# SCH_SGU-Ring.net
KiCad netlist of a schematic drawn in EasyEDA
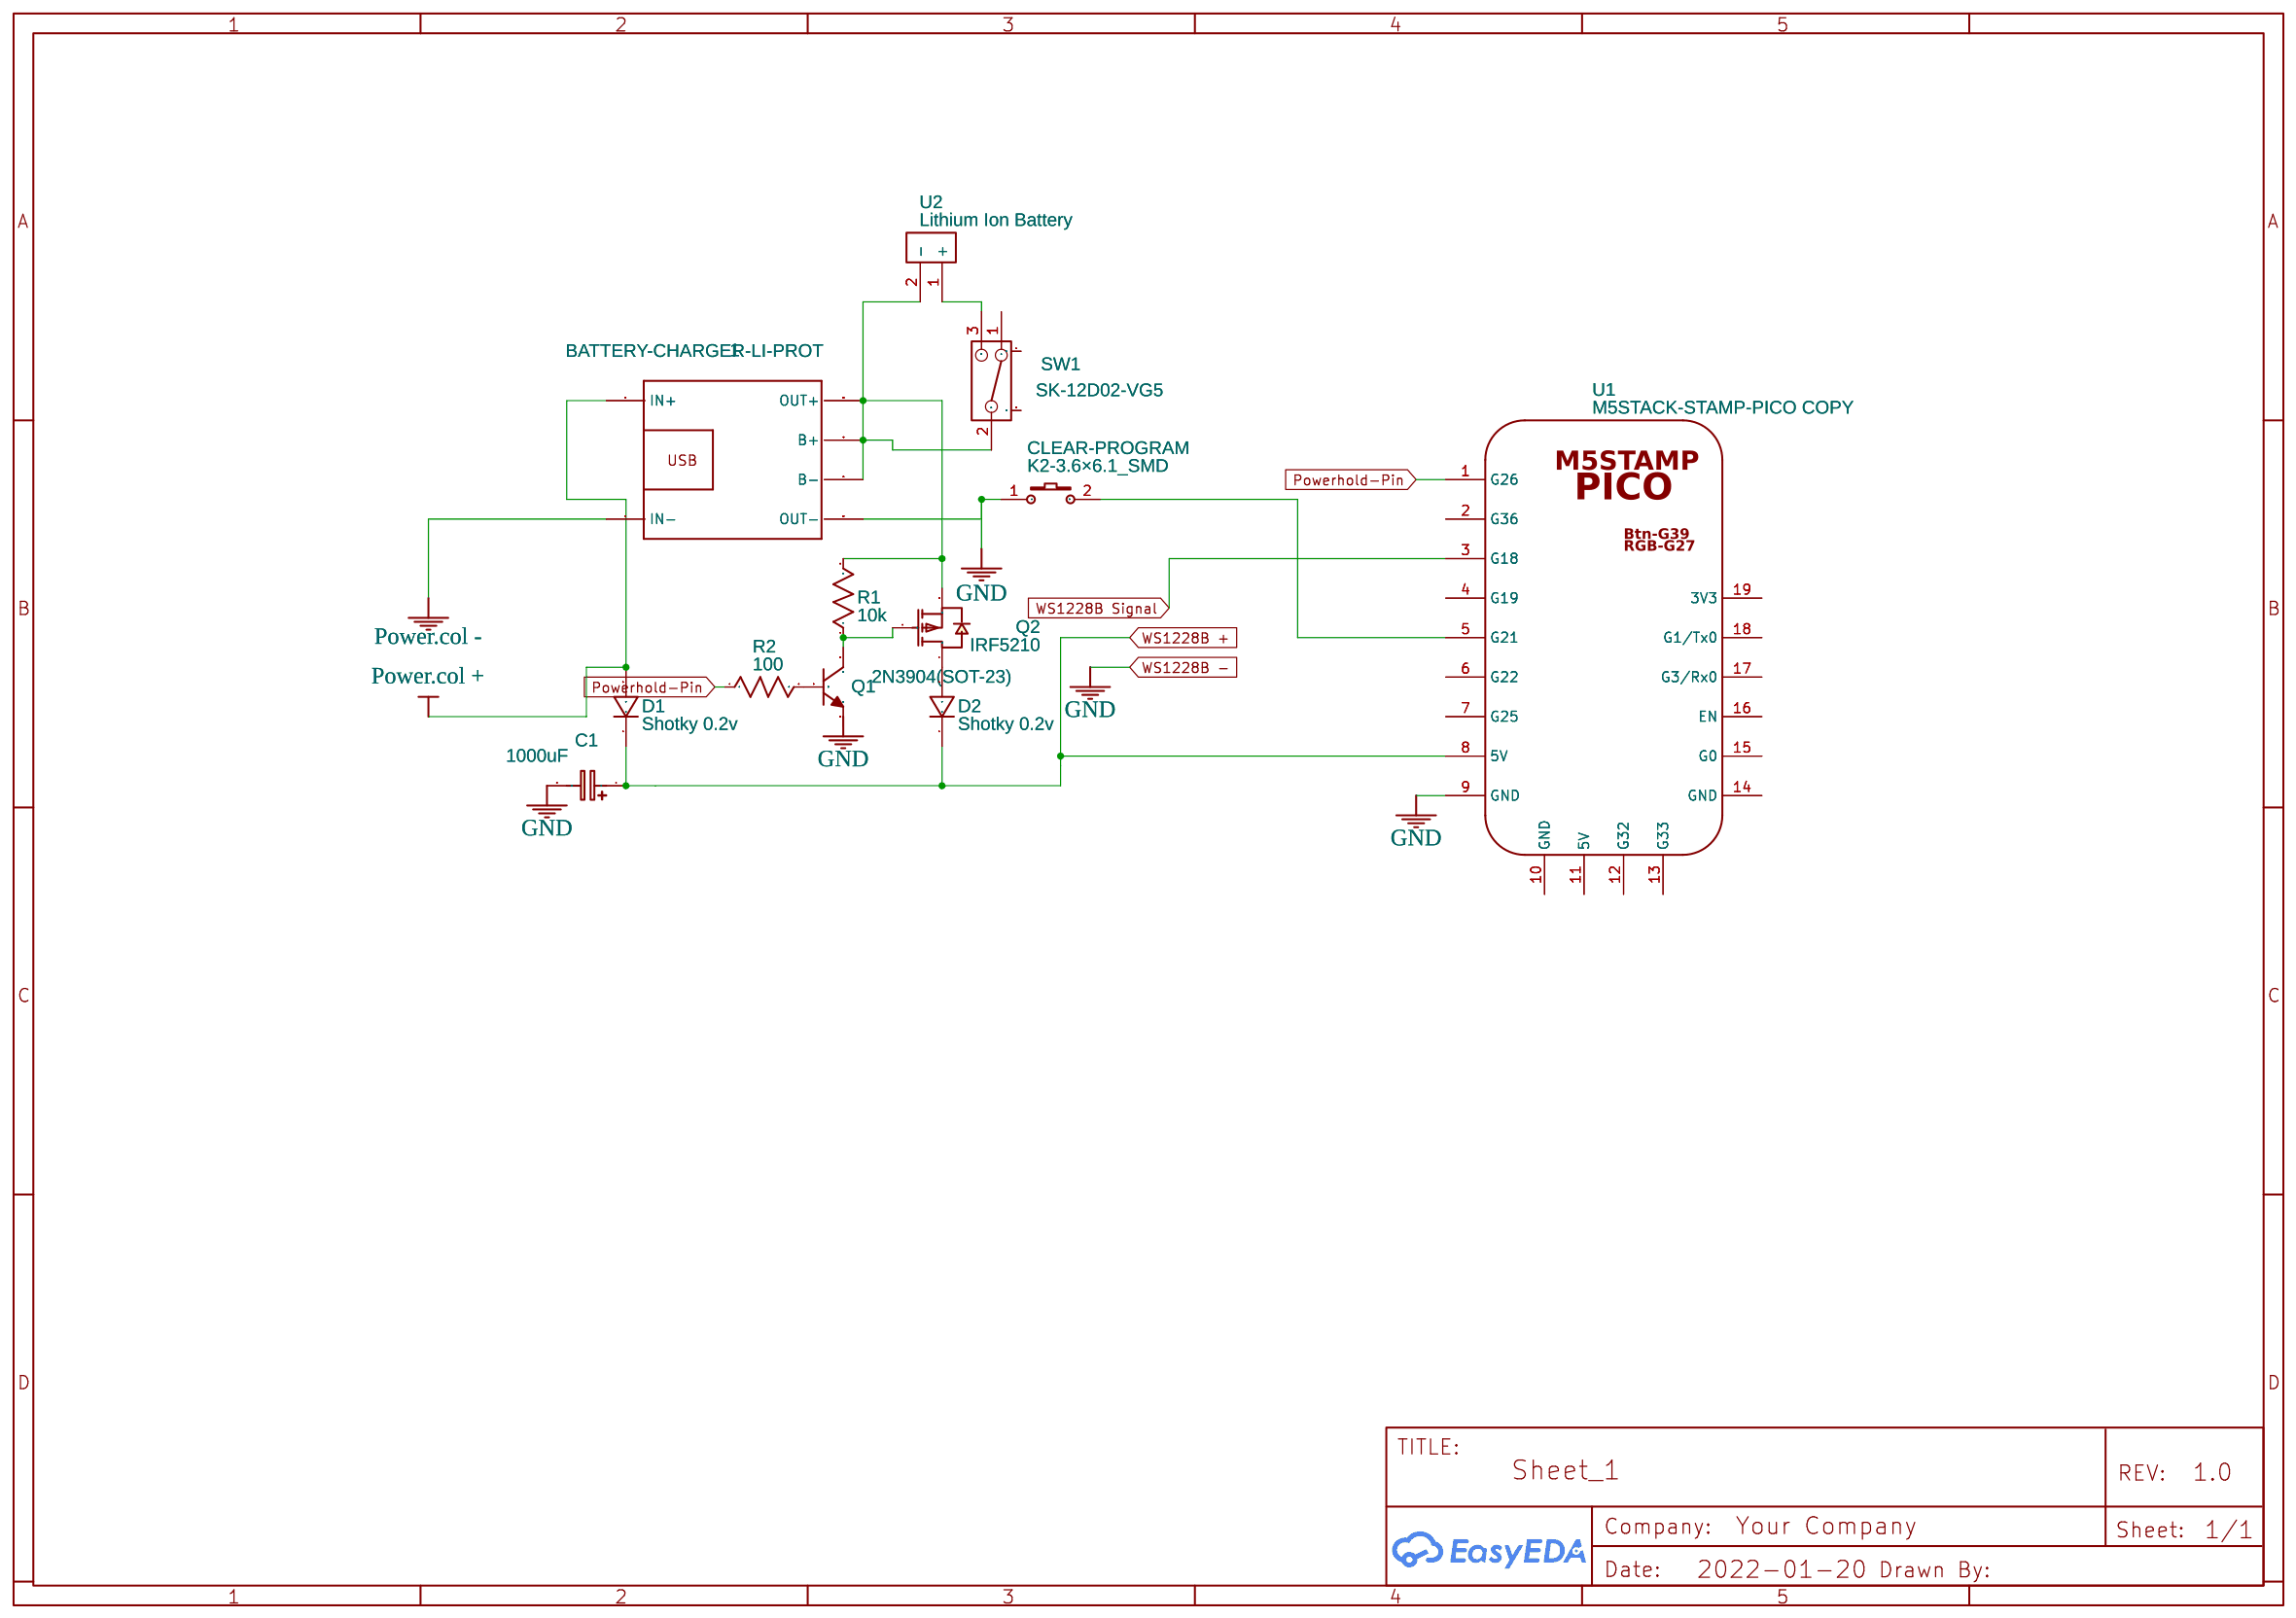
[diagram p0: schematic sheet]

(export (version "E")
  (design (tool "Eeschema 10.0.6"))
  (components
    (comp (ref "1") (value "BATTERY-CHARGER-LI-PROT") (libsource (lib "") (part "BATTERY-CHARGER-LI-PROT")))
    (comp (ref "C1") (value "1000uF") (libsource (lib "") (part "C_Tan_SMD_A_EU")))
    (comp (ref "CLEAR-PROGRAM")
      (value "K2-3.6×6.1_SMD")
      (fields
        (field (name "BOM_Manufacturer Part") "K2-1107ST-A4SW-06")
        (field (name "BOM_Supplier Part") "C118141")
      )
      (libsource (lib "") (part "K2-3.6×6.1_SMD"))
    )
    (comp (ref "D1")
      (value "Shotky 0.2v")
      (fields (field (name "BOM_Manufacturer Part") "1N4007W") (field (name "BOM_Supplier Part") "C328592"))
      (libsource (lib "") (part "1N4007W"))
    )
    (comp (ref "D2")
      (value "Shotky 0.2v")
      (fields (field (name "BOM_Manufacturer Part") "1N4007W") (field (name "BOM_Supplier Part") "C328592"))
      (libsource (lib "") (part "1N4007W"))
    )
    (comp (ref "Q1")
      (value "2N3904(SOT-23)")
      (fields
        (field (name "BOM_Manufacturer Part") "2n3904S-RTK/PS")
        (field (name "BOM_Supplier Part") "C18536")
      )
      (libsource (lib "") (part "2N3904(SOT-23)"))
    )
    (comp (ref "Q2")
      (value "IRF5210")
      (fields
        (field (name "BOM_Manufacturer Part") "IRF5210STRLPBF")
        (field (name "BOM_Supplier Part") "C2622")
      )
      (libsource (lib "") (part "IRF5210"))
    )
    (comp (ref "R1") (value "10k") (libsource (lib "") (part "R_0603_US")))
    (comp (ref "R2") (value "100") (libsource (lib "") (part "R_0603_US_1")))
    (comp (ref "SW1")
      (value "SK-12D02-VG5")
      (fields (field (name "BOM_Supplier Part") "C136722"))
      (libsource (lib "") (part "SK-12D02-VG5"))
    )
    (comp (ref "U1") (value "M5STACK-STAMP-PICO COPY") (libsource (lib "") (part "M5STACK-STAMP-PICO COPY")))
    (comp (ref "U2") (value "Lithium Ion Battery") (libsource (lib "") (part "Lithium Ion Battery")))
  )
  (nets
    (net (code "1") (name "Net-(Q1-B)") (class "Default")
      (node (ref "Q1") (pin "2") (pinfunction "B_2") (pintype "input"))
      (node (ref "R2") (pin "2") (pinfunction "2_2") (pintype "unspecified"))
    )
    (net (code "2") (name "Net-(Q1-C)") (class "Default")
      (node (ref "Q1") (pin "3") (pinfunction "C_3") (pintype "input"))
      (node (ref "Q2") (pin "1") (pinfunction "G_1") (pintype "unspecified"))
      (node (ref "R1") (pin "1") (pinfunction "1_1") (pintype "unspecified"))
    )
    (net (code "3") (name "Net-(Q2-D)") (class "Default")
      (node (ref "D2") (pin "2") (pinfunction "2_2") (pintype "unspecified"))
      (node (ref "Q2") (pin "4") (pinfunction "D_4") (pintype "unspecified"))
    )
    (net (code "4") (name "Net-(Q2-S)") (class "Default")
      (node (ref "1") (pin "B+") (pinfunction "B+_B+") (pintype "bidirectional"))
      (node (ref "1") (pin "B-") (pinfunction "B-_B-") (pintype "bidirectional"))
      (node (ref "1") (pin "OUT+") (pinfunction "OUT+_OUT+") (pintype "bidirectional"))
      (node (ref "Q2") (pin "3") (pinfunction "S_3") (pintype "unspecified"))
      (node (ref "R1") (pin "2") (pinfunction "2_2") (pintype "unspecified"))
      (node (ref "SW1") (pin "2") (pinfunction "2_2") (pintype "unspecified"))
      (node (ref "U2") (pin "2") (pinfunction "-_2") (pintype "unspecified"))
    )
    (net (code "5") (name "Net-(U1-G21)") (class "Default")
      (node (ref "CLEAR-PROGRAM") (pin "2") (pinfunction "2_2") (pintype "unspecified"))
      (node (ref "U1") (pin "5") (pinfunction "G21_5") (pintype "unspecified"))
    )
    (net (code "6") (name "Net-(U2-+)") (class "Default")
      (node (ref "SW1") (pin "3") (pinfunction "3_3") (pintype "unspecified"))
      (node (ref "U2") (pin "1") (pinfunction "+_1") (pintype "unspecified"))
    )
    (net (code "7") (name "Power.col +") (class "Default")
      (node (ref "1") (pin "IN+") (pinfunction "IN+_IN+") (pintype "bidirectional"))
      (node (ref "D1") (pin "2") (pinfunction "2_2") (pintype "unspecified"))
    )
    (net (code "8") (name "Power.col -") (class "Default")
      (node (ref "1") (pin "IN-") (pinfunction "IN-_IN-") (pintype "bidirectional"))
    )
    (net (code "9") (name "Powerhold-Pin") (class "Default")
      (node (ref "R2") (pin "1") (pinfunction "1_1") (pintype "unspecified"))
      (node (ref "U1") (pin "1") (pinfunction "G26_1") (pintype "unspecified"))
    )
    (net (code "10") (name "WS1228B +") (class "Default")
      (node (ref "C1") (pin "1") (pinfunction "1_1") (pintype "unspecified"))
      (node (ref "D1") (pin "1") (pinfunction "1_1") (pintype "unspecified"))
      (node (ref "D2") (pin "1") (pinfunction "1_1") (pintype "unspecified"))
      (node (ref "U1") (pin "8") (pinfunction "5V_8") (pintype "unspecified"))
    )
    (net (code "11") (name "WS1228B -") (class "Default")
      (node (ref "1") (pin "OUT-") (pinfunction "OUT-_OUT-") (pintype "bidirectional"))
      (node (ref "C1") (pin "2") (pinfunction "2_2") (pintype "unspecified"))
      (node (ref "CLEAR-PROGRAM") (pin "1") (pinfunction "1_1") (pintype "unspecified"))
      (node (ref "Q1") (pin "1") (pinfunction "E_1") (pintype "input"))
      (node (ref "U1") (pin "9") (pinfunction "GND_9") (pintype "unspecified"))
    )
    (net (code "12") (name "WS1228B Signal") (class "Default")
      (node (ref "U1") (pin "3") (pinfunction "G18_3") (pintype "unspecified"))
    )
    (net (code "13") (name "unconnected-(SW1-Pad1)") (class "Default")
      (node (ref "SW1") (pin "1") (pinfunction "1_1") (pintype "unspecified"))
    )
    (net (code "14") (name "unconnected-(SW1-Pad4)") (class "Default")
      (node (ref "SW1") (pin "4") (pinfunction "4_4") (pintype "unspecified"))
    )
    (net (code "15") (name "unconnected-(SW1-Pad5)") (class "Default")
      (node (ref "SW1") (pin "5") (pinfunction "5_5") (pintype "unspecified"))
    )
    (net (code "16") (name "unconnected-(U1-3V3-Pad19)") (class "Default")
      (node (ref "U1") (pin "19") (pinfunction "3V3_19") (pintype "unspecified"))
    )
    (net (code "17") (name "unconnected-(U1-5V-Pad11)") (class "Default")
      (node (ref "U1") (pin "11") (pinfunction "5V_11") (pintype "unspecified"))
    )
    (net (code "18") (name "unconnected-(U1-EN-Pad16)") (class "Default")
      (node (ref "U1") (pin "16") (pinfunction "EN_16") (pintype "unspecified"))
    )
    (net (code "19") (name "unconnected-(U1-G0-Pad15)") (class "Default")
      (node (ref "U1") (pin "15") (pinfunction "G0_15") (pintype "unspecified"))
    )
    (net (code "20") (name "unconnected-(U1-G1{slash}Tx0-Pad18)") (class "Default")
      (node (ref "U1") (pin "18") (pinfunction "G1/Tx0_18") (pintype "unspecified"))
    )
    (net (code "21") (name "unconnected-(U1-G3{slash}Rx0-Pad17)") (class "Default")
      (node (ref "U1") (pin "17") (pinfunction "G3/Rx0_17") (pintype "unspecified"))
    )
    (net (code "22") (name "unconnected-(U1-G19-Pad4)") (class "Default")
      (node (ref "U1") (pin "4") (pinfunction "G19_4") (pintype "unspecified"))
    )
    (net (code "23") (name "unconnected-(U1-G22-Pad6)") (class "Default")
      (node (ref "U1") (pin "6") (pinfunction "G22_6") (pintype "unspecified"))
    )
    (net (code "24") (name "unconnected-(U1-G25-Pad7)") (class "Default")
      (node (ref "U1") (pin "7") (pinfunction "G25_7") (pintype "unspecified"))
    )
    (net (code "25") (name "unconnected-(U1-G32-Pad12)") (class "Default")
      (node (ref "U1") (pin "12") (pinfunction "G32_12") (pintype "unspecified"))
    )
    (net (code "26") (name "unconnected-(U1-G33-Pad13)") (class "Default")
      (node (ref "U1") (pin "13") (pinfunction "G33_13") (pintype "unspecified"))
    )
    (net (code "27") (name "unconnected-(U1-G36-Pad2)") (class "Default")
      (node (ref "U1") (pin "2") (pinfunction "G36_2") (pintype "unspecified"))
    )
    (net (code "28") (name "unconnected-(U1-GND-Pad10)") (class "Default")
      (node (ref "U1") (pin "10") (pinfunction "GND_10") (pintype "unspecified"))
    )
    (net (code "29") (name "unconnected-(U1-GND-Pad14)") (class "Default")
      (node (ref "U1") (pin "14") (pinfunction "GND_14") (pintype "unspecified"))
    )
  )
)
